# watch_mb.net
KiCad netlist of a schematic drawn in EAGLE
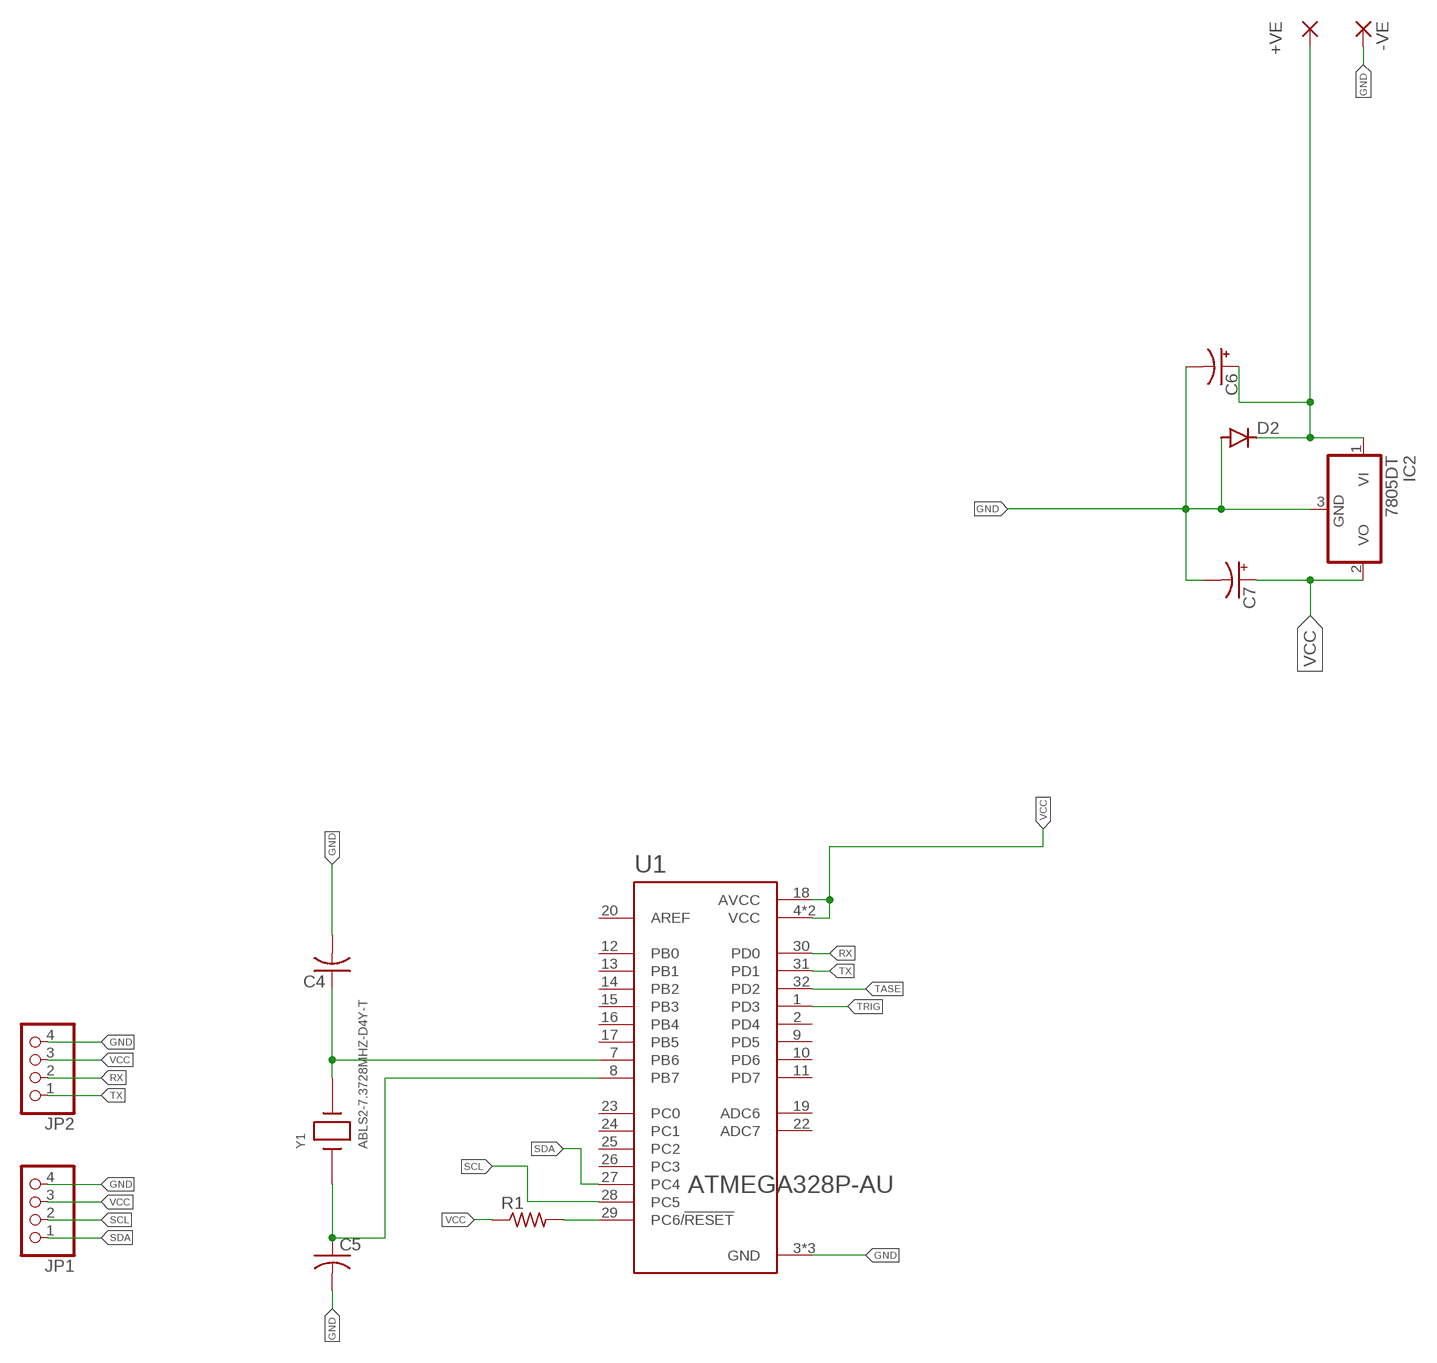
[diagram p0: schematic, sheet 1]

(export (version "E")
  (design (tool "Eeschema 10.0.6"))
  (components
    (comp (ref "+VE")
      (value "WIREPAD1,6/0,8")
      (footprint "eagle-import:1,6_0,8")
      (libsource (lib "eagle-import") (part "WIREPAD1,6/0,8"))
    )
    (comp (ref "-VE")
      (value "WIREPAD1,6/0,8")
      (footprint "eagle-import:1,6_0,8")
      (libsource (lib "eagle-import") (part "WIREPAD1,6/0,8"))
    )
    (comp (ref "C4")
      (value "C-US025-024X044")
      (footprint "eagle-import:C025-024X044")
      (libsource (lib "eagle-import") (part "C-US025-024X044"))
    )
    (comp (ref "C5")
      (value "C-US025-024X044")
      (footprint "eagle-import:C025-024X044")
      (libsource (lib "eagle-import") (part "C-US025-024X044"))
    )
    (comp (ref "C6")
      (value "CPOL-US153CLV-1010")
      (footprint "eagle-import:153CLV-1010")
      (libsource (lib "eagle-import") (part "CPOL-US153CLV-1010"))
    )
    (comp (ref "C7")
      (value "CPOL-US153CLV-1010")
      (footprint "eagle-import:153CLV-1010")
      (libsource (lib "eagle-import") (part "CPOL-US153CLV-1010"))
    )
    (comp (ref "D2")
      (value "DIODE-DO214AC")
      (footprint "eagle-import:DO214AC")
      (libsource (lib "eagle-import") (part "DIODE-DO214AC"))
    )
    (comp (ref "IC2")
      (value "7805DT")
      (footprint "eagle-import:TO252")
      (libsource (lib "eagle-import") (part "78DT05"))
    )
    (comp (ref "JP1")
      (value "PINHD-1X4")
      (footprint "eagle-import:1X04")
      (libsource (lib "eagle-import") (part "PINHD-1X4"))
    )
    (comp (ref "JP2")
      (value "PINHD-1X4")
      (footprint "eagle-import:1X04")
      (libsource (lib "eagle-import") (part "PINHD-1X4"))
    )
    (comp (ref "R1")
      (value "R-US_R0603")
      (footprint "eagle-import:R0603")
      (libsource (lib "eagle-import") (part "R-US_R0603"))
    )
    (comp (ref "U1")
      (value "ATMEGA328P-AU")
      (footprint "eagle-import:QFP80P900X900X120-32N")
      (fields (field (name "MF") "Microchip Technology"))
      (libsource (lib "eagle-import") (part "ATMEGA328P-AU"))
    )
    (comp (ref "Y1")
      (value "ABLS2-7.3728MHZ-D4Y-T")
      (footprint "eagle-import:XTAL_ABLS2-7.3728MHZ-D4Y-T")
      (fields (field (name "MF") "Abracon"))
      (libsource (lib "eagle-import") (part "ABLS2-7.3728MHZ-D4Y-T"))
    )
  )
  (nets
    (net (code "1") (name "GND") (class "Default")
      (node (ref "-VE") (pin "1") (pinfunction "P_1") (pintype "passive"))
      (node (ref "C4") (pin "2") (pinfunction "2_2") (pintype "passive"))
      (node (ref "C5") (pin "2") (pinfunction "2_2") (pintype "passive"))
      (node (ref "C6") (pin "-") (pinfunction "-_-") (pintype "passive"))
      (node (ref "C7") (pin "-") (pinfunction "-_-") (pintype "passive"))
      (node (ref "D2") (pin "A") (pinfunction "A_A") (pintype "passive"))
      (node (ref "IC2") (pin "3") (pinfunction "GND_3") (pintype "passive"))
      (node (ref "JP1") (pin "4") (pinfunction "4_4") (pintype "passive"))
      (node (ref "JP2") (pin "4") (pinfunction "4_4") (pintype "passive"))
      (node (ref "U1") (pin "21") (pinfunction "GND_21") (pintype "power_in"))
      (node (ref "U1") (pin "3") (pinfunction "GND_3") (pintype "power_in"))
      (node (ref "U1") (pin "5") (pinfunction "GND_5") (pintype "power_in"))
    )
    (net (code "2") (name "Net-(+VE-P)") (class "Default")
      (node (ref "+VE") (pin "1") (pinfunction "P_1") (pintype "passive"))
      (node (ref "C6") (pin "+") (pinfunction "+_+") (pintype "passive"))
      (node (ref "D2") (pin "C") (pinfunction "C_C") (pintype "passive"))
      (node (ref "IC2") (pin "1") (pinfunction "VI_1") (pintype "input"))
    )
    (net (code "3") (name "Net-(U1-PB6)") (class "Default")
      (node (ref "C4") (pin "1") (pinfunction "1_1") (pintype "passive"))
      (node (ref "U1") (pin "7") (pinfunction "PB6_7") (pintype "bidirectional"))
      (node (ref "Y1") (pin "2") (pinfunction "2_2") (pintype "passive"))
    )
    (net (code "4") (name "Net-(U1-PB7)") (class "Default")
      (node (ref "C5") (pin "1") (pinfunction "1_1") (pintype "passive"))
      (node (ref "U1") (pin "8") (pinfunction "PB7_8") (pintype "bidirectional"))
      (node (ref "Y1") (pin "1") (pinfunction "1_1") (pintype "passive"))
    )
    (net (code "5") (name "Net-(U1-PC6{slash}~{RESET})") (class "Default")
      (node (ref "R1") (pin "2") (pinfunction "2_2") (pintype "passive"))
      (node (ref "U1") (pin "29") (pinfunction "PC6/~{RESET}_29") (pintype "bidirectional"))
    )
    (net (code "6") (name "RX") (class "Default")
      (node (ref "JP2") (pin "2") (pinfunction "2_2") (pintype "passive"))
      (node (ref "U1") (pin "30") (pinfunction "PD0_30") (pintype "bidirectional"))
    )
    (net (code "7") (name "SCL") (class "Default")
      (node (ref "JP1") (pin "2") (pinfunction "2_2") (pintype "passive"))
      (node (ref "U1") (pin "28") (pinfunction "PC5_28") (pintype "bidirectional"))
    )
    (net (code "8") (name "SDA") (class "Default")
      (node (ref "JP1") (pin "1") (pinfunction "1_1") (pintype "passive"))
      (node (ref "U1") (pin "27") (pinfunction "PC4_27") (pintype "bidirectional"))
    )
    (net (code "9") (name "TASE") (class "Default")
      (node (ref "U1") (pin "32") (pinfunction "PD2_32") (pintype "bidirectional"))
    )
    (net (code "10") (name "TRIG") (class "Default")
      (node (ref "U1") (pin "1") (pinfunction "PD3_1") (pintype "bidirectional"))
    )
    (net (code "11") (name "TX") (class "Default")
      (node (ref "JP2") (pin "1") (pinfunction "1_1") (pintype "passive"))
      (node (ref "U1") (pin "31") (pinfunction "PD1_31") (pintype "bidirectional"))
    )
    (net (code "12") (name "VCC") (class "Default")
      (node (ref "C7") (pin "+") (pinfunction "+_+") (pintype "passive"))
      (node (ref "IC2") (pin "2") (pinfunction "VO_2") (pintype "passive"))
      (node (ref "JP1") (pin "3") (pinfunction "3_3") (pintype "passive"))
      (node (ref "JP2") (pin "3") (pinfunction "3_3") (pintype "passive"))
      (node (ref "R1") (pin "1") (pinfunction "1_1") (pintype "passive"))
      (node (ref "U1") (pin "18") (pinfunction "AVCC_18") (pintype "power_in"))
      (node (ref "U1") (pin "4") (pinfunction "VCC_4") (pintype "power_in"))
      (node (ref "U1") (pin "6") (pinfunction "VCC_6") (pintype "power_in"))
    )
    (net (code "13") (name "unconnected-(U1-ADC6-Pad19)") (class "Default")
      (node (ref "U1") (pin "19") (pinfunction "ADC6_19") (pintype "bidirectional"))
    )
    (net (code "14") (name "unconnected-(U1-ADC7-Pad22)") (class "Default")
      (node (ref "U1") (pin "22") (pinfunction "ADC7_22") (pintype "bidirectional"))
    )
    (net (code "15") (name "unconnected-(U1-AREF-Pad20)") (class "Default")
      (node (ref "U1") (pin "20") (pinfunction "AREF_20") (pintype "input"))
    )
    (net (code "16") (name "unconnected-(U1-PB0-Pad12)") (class "Default")
      (node (ref "U1") (pin "12") (pinfunction "PB0_12") (pintype "bidirectional"))
    )
    (net (code "17") (name "unconnected-(U1-PB1-Pad13)") (class "Default")
      (node (ref "U1") (pin "13") (pinfunction "PB1_13") (pintype "bidirectional"))
    )
    (net (code "18") (name "unconnected-(U1-PB2-Pad14)") (class "Default")
      (node (ref "U1") (pin "14") (pinfunction "PB2_14") (pintype "bidirectional"))
    )
    (net (code "19") (name "unconnected-(U1-PB3-Pad15)") (class "Default")
      (node (ref "U1") (pin "15") (pinfunction "PB3_15") (pintype "bidirectional"))
    )
    (net (code "20") (name "unconnected-(U1-PB4-Pad16)") (class "Default")
      (node (ref "U1") (pin "16") (pinfunction "PB4_16") (pintype "bidirectional"))
    )
    (net (code "21") (name "unconnected-(U1-PB5-Pad17)") (class "Default")
      (node (ref "U1") (pin "17") (pinfunction "PB5_17") (pintype "bidirectional"))
    )
    (net (code "22") (name "unconnected-(U1-PC0-Pad23)") (class "Default")
      (node (ref "U1") (pin "23") (pinfunction "PC0_23") (pintype "bidirectional"))
    )
    (net (code "23") (name "unconnected-(U1-PC1-Pad24)") (class "Default")
      (node (ref "U1") (pin "24") (pinfunction "PC1_24") (pintype "bidirectional"))
    )
    (net (code "24") (name "unconnected-(U1-PC2-Pad25)") (class "Default")
      (node (ref "U1") (pin "25") (pinfunction "PC2_25") (pintype "bidirectional"))
    )
    (net (code "25") (name "unconnected-(U1-PC3-Pad26)") (class "Default")
      (node (ref "U1") (pin "26") (pinfunction "PC3_26") (pintype "bidirectional"))
    )
    (net (code "26") (name "unconnected-(U1-PD4-Pad2)") (class "Default")
      (node (ref "U1") (pin "2") (pinfunction "PD4_2") (pintype "bidirectional"))
    )
    (net (code "27") (name "unconnected-(U1-PD5-Pad9)") (class "Default")
      (node (ref "U1") (pin "9") (pinfunction "PD5_9") (pintype "bidirectional"))
    )
    (net (code "28") (name "unconnected-(U1-PD6-Pad10)") (class "Default")
      (node (ref "U1") (pin "10") (pinfunction "PD6_10") (pintype "bidirectional"))
    )
    (net (code "29") (name "unconnected-(U1-PD7-Pad11)") (class "Default")
      (node (ref "U1") (pin "11") (pinfunction "PD7_11") (pintype "bidirectional"))
    )
  )
)
